# ArdinoCheaterBoardSche.net
KiCad netlist of a schematic drawn in EAGLE
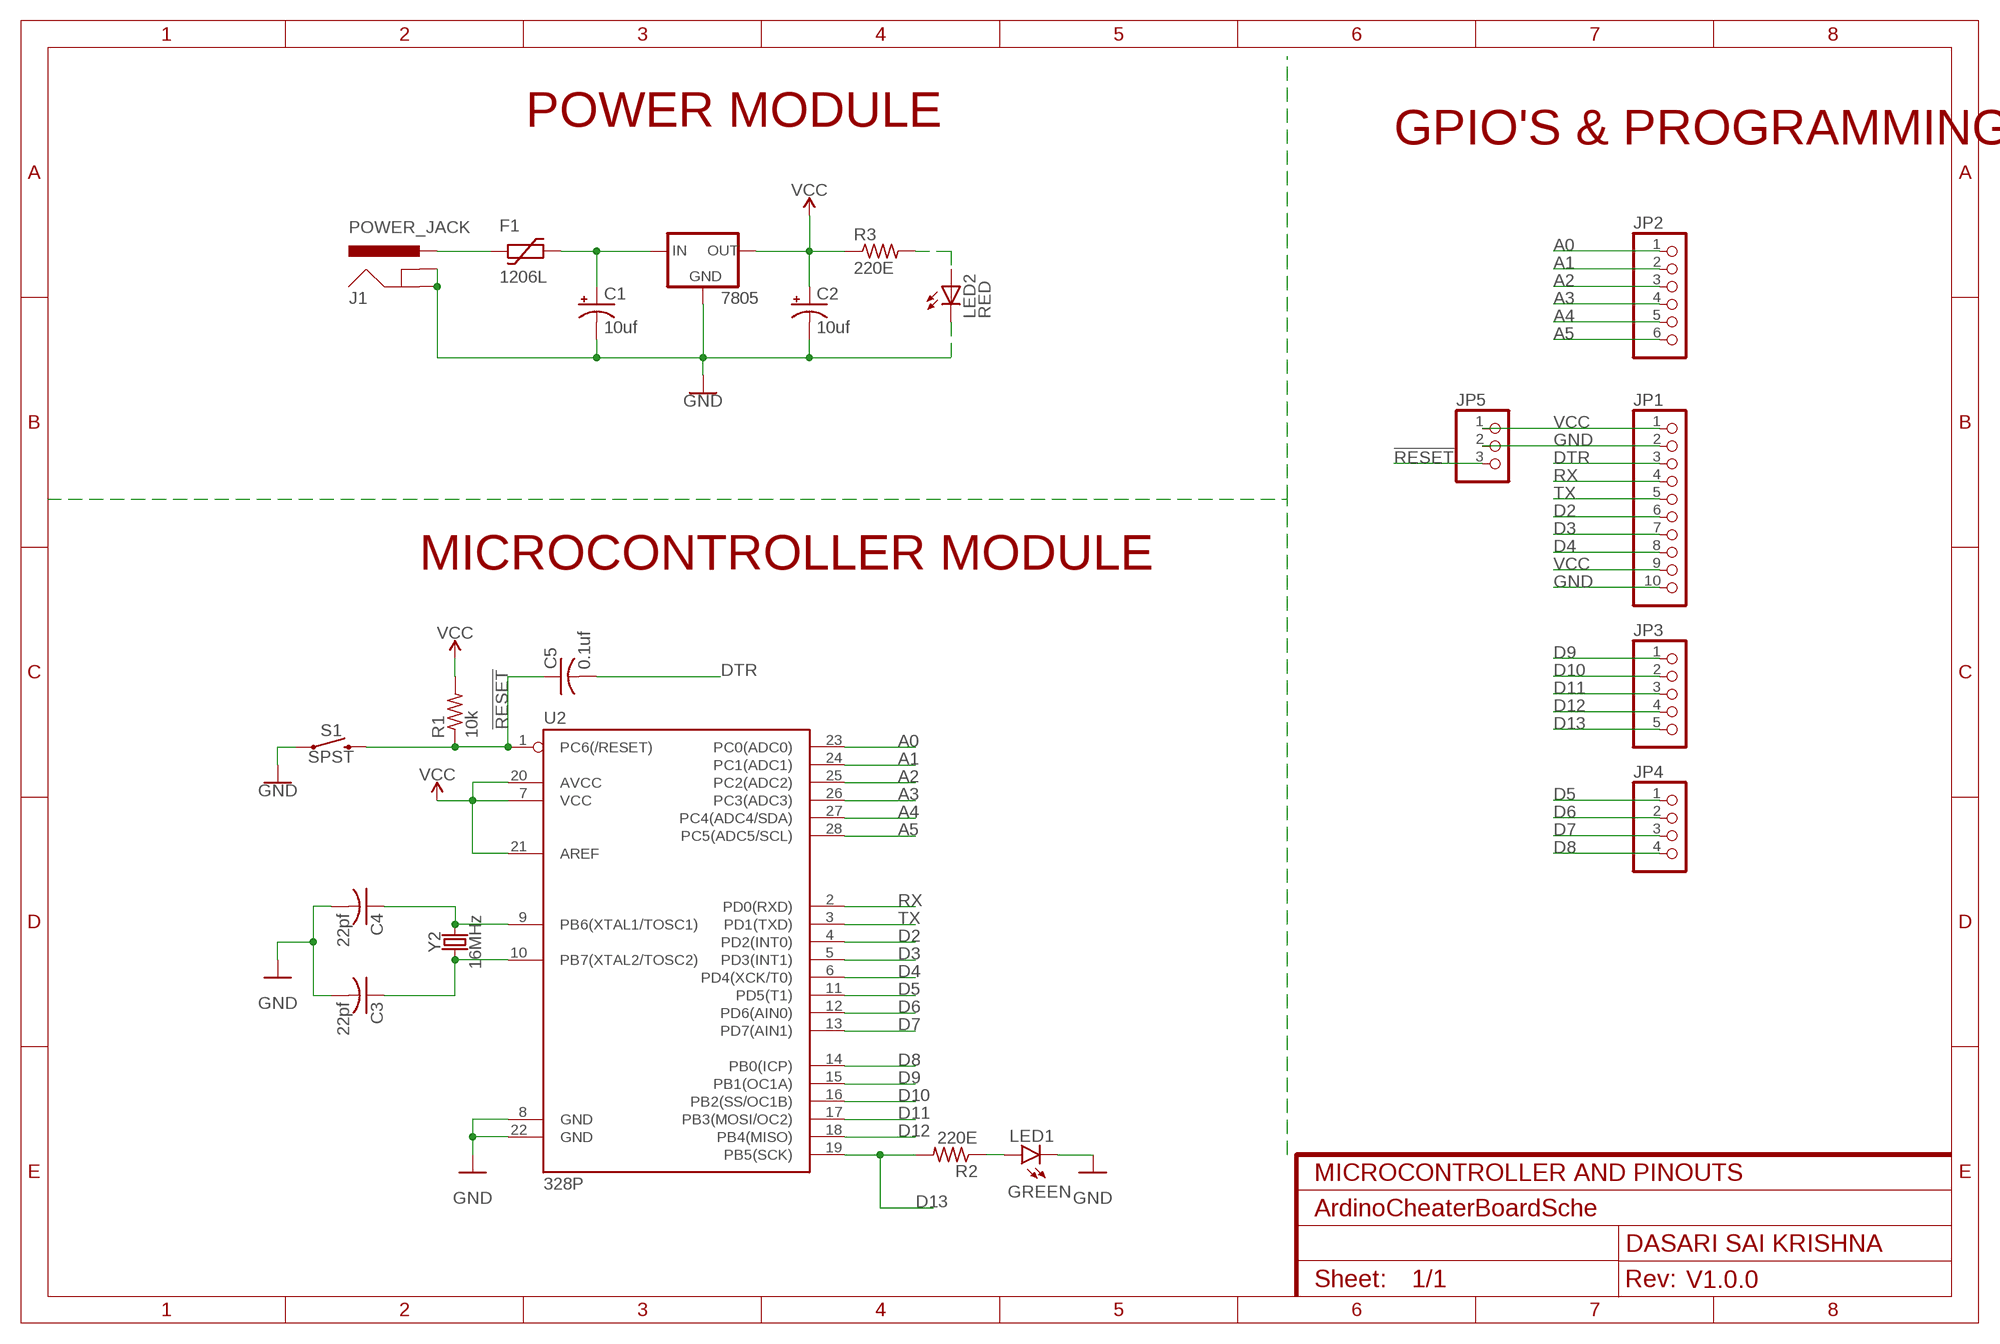
[diagram p0: schematic, sheet 1]

(export (version "E")
  (design (tool "Eeschema 10.0.6"))
  (components
    (comp (ref "C1")
      (value "10uf")
      (footprint "eagle-import:E2,5-6E")
      (libsource (lib "eagle-import") (part "CPOL-USE2,5-6E"))
    )
    (comp (ref "C2")
      (value "10uf")
      (footprint "eagle-import:E2,5-6E")
      (libsource (lib "eagle-import") (part "CPOL-USE2,5-6E"))
    )
    (comp (ref "C3")
      (value "22pf")
      (footprint "eagle-import:C025-024X044")
      (libsource (lib "eagle-import") (part "C-US025-024X044"))
    )
    (comp (ref "C4")
      (value "22pf")
      (footprint "eagle-import:C025-024X044")
      (libsource (lib "eagle-import") (part "C-US025-024X044"))
    )
    (comp (ref "C5")
      (value "0.1uf")
      (footprint "eagle-import:C025-024X044")
      (libsource (lib "eagle-import") (part "C-US025-024X044"))
    )
    (comp (ref "F1")
      (value "1206L")
      (footprint "eagle-import:1206L")
      (libsource (lib "eagle-import") (part "1206L"))
    )
    (comp (ref "IC1")
      (value "7805")
      (footprint "eagle-import:78XXS")
      (libsource (lib "eagle-import") (part "78XXS"))
    )
    (comp (ref "J1")
      (value "POWER_JACK")
      (footprint "eagle-import:POWER_JACK_PTH")
      (libsource (lib "eagle-import") (part "POWER_JACK"))
    )
    (comp (ref "JP1")
      (value "PINHD-1X10")
      (footprint "eagle-import:1X10")
      (libsource (lib "eagle-import") (part "PINHD-1X10"))
    )
    (comp (ref "JP2")
      (value "PINHD-1X6")
      (footprint "eagle-import:1X06")
      (libsource (lib "eagle-import") (part "PINHD-1X6"))
    )
    (comp (ref "JP3")
      (value "PINHD-1X5")
      (footprint "eagle-import:1X05")
      (libsource (lib "eagle-import") (part "PINHD-1X5"))
    )
    (comp (ref "JP4")
      (value "PINHD-1X4")
      (footprint "eagle-import:1X04")
      (libsource (lib "eagle-import") (part "PINHD-1X4"))
    )
    (comp (ref "JP5")
      (value "PINHD-1X3")
      (footprint "eagle-import:1X03")
      (libsource (lib "eagle-import") (part "PINHD-1X3"))
    )
    (comp (ref "LED1")
      (value "GREEN")
      (footprint "eagle-import:LED3MM")
      (libsource (lib "eagle-import") (part "led_259_LED3MM"))
    )
    (comp (ref "LED2")
      (value "RED")
      (footprint "eagle-import:LED3MM")
      (libsource (lib "eagle-import") (part "LED3MM"))
    )
    (comp (ref "R1")
      (value "10k")
      (footprint "eagle-import:0204_7")
      (libsource (lib "eagle-import") (part "R-US_0204/7"))
    )
    (comp (ref "R2")
      (value "220E")
      (footprint "eagle-import:0204_7")
      (libsource (lib "eagle-import") (part "R-US_0204/7"))
    )
    (comp (ref "R3")
      (value "220E")
      (footprint "eagle-import:0204_7")
      (libsource (lib "eagle-import") (part "R-US_0204/7"))
    )
    (comp (ref "S1")
      (value "SPST")
      (footprint "eagle-import:TACTILE_SWITCH_PTH_6.0MM")
      (libsource (lib "eagle-import") (part "MOMENTARY-SWITCH-SPST-PTH-6.0MM"))
    )
    (comp (ref "U2")
      (value "328P")
      (footprint "eagle-import:DIP28")
      (libsource (lib "eagle-import") (part "ATMEGA328P_PDIP"))
    )
    (comp (ref "Y2")
      (value "16MHz")
      (footprint "eagle-import:HC49US")
      (libsource (lib "eagle-import") (part "CRYSTAL-16MHZPTH-HC49US"))
    )
  )
  (nets
    (net (code "1") (name "/A0") (class "Default")
      (node (ref "JP2") (pin "1") (pinfunction "1_1") (pintype "passive"))
      (node (ref "U2") (pin "23") (pinfunction "PC0(ADC0)_23") (pintype "bidirectional"))
    )
    (net (code "2") (name "/A1") (class "Default")
      (node (ref "JP2") (pin "2") (pinfunction "2_2") (pintype "passive"))
      (node (ref "U2") (pin "24") (pinfunction "PC1(ADC1)_24") (pintype "bidirectional"))
    )
    (net (code "3") (name "/A2") (class "Default")
      (node (ref "JP2") (pin "3") (pinfunction "3_3") (pintype "passive"))
      (node (ref "U2") (pin "25") (pinfunction "PC2(ADC2)_25") (pintype "bidirectional"))
    )
    (net (code "4") (name "/A3") (class "Default")
      (node (ref "JP2") (pin "4") (pinfunction "4_4") (pintype "passive"))
      (node (ref "U2") (pin "26") (pinfunction "PC3(ADC3)_26") (pintype "bidirectional"))
    )
    (net (code "5") (name "/A4") (class "Default")
      (node (ref "JP2") (pin "5") (pinfunction "5_5") (pintype "passive"))
      (node (ref "U2") (pin "27") (pinfunction "PC4(ADC4/SDA)_27") (pintype "bidirectional"))
    )
    (net (code "6") (name "/A5") (class "Default")
      (node (ref "JP2") (pin "6") (pinfunction "6_6") (pintype "passive"))
      (node (ref "U2") (pin "28") (pinfunction "PC5(ADC5/SCL)_28") (pintype "bidirectional"))
    )
    (net (code "7") (name "/D2") (class "Default")
      (node (ref "JP1") (pin "6") (pinfunction "6_6") (pintype "passive"))
      (node (ref "U2") (pin "4") (pinfunction "PD2(INT0)_4") (pintype "bidirectional"))
    )
    (net (code "8") (name "/D3") (class "Default")
      (node (ref "JP1") (pin "7") (pinfunction "7_7") (pintype "passive"))
      (node (ref "U2") (pin "5") (pinfunction "PD3(INT1)_5") (pintype "bidirectional"))
    )
    (net (code "9") (name "/D4") (class "Default")
      (node (ref "JP1") (pin "8") (pinfunction "8_8") (pintype "passive"))
      (node (ref "U2") (pin "6") (pinfunction "PD4(XCK/T0)_6") (pintype "bidirectional"))
    )
    (net (code "10") (name "/D5") (class "Default")
      (node (ref "JP4") (pin "1") (pinfunction "1_1") (pintype "passive"))
      (node (ref "U2") (pin "11") (pinfunction "PD5(T1)_11") (pintype "bidirectional"))
    )
    (net (code "11") (name "/D6") (class "Default")
      (node (ref "JP4") (pin "2") (pinfunction "2_2") (pintype "passive"))
      (node (ref "U2") (pin "12") (pinfunction "PD6(AIN0)_12") (pintype "bidirectional"))
    )
    (net (code "12") (name "/D7") (class "Default")
      (node (ref "JP4") (pin "3") (pinfunction "3_3") (pintype "passive"))
      (node (ref "U2") (pin "13") (pinfunction "PD7(AIN1)_13") (pintype "bidirectional"))
    )
    (net (code "13") (name "/D8") (class "Default")
      (node (ref "JP4") (pin "4") (pinfunction "4_4") (pintype "passive"))
      (node (ref "U2") (pin "14") (pinfunction "PB0(ICP)_14") (pintype "bidirectional"))
    )
    (net (code "14") (name "/D9") (class "Default")
      (node (ref "JP3") (pin "1") (pinfunction "1_1") (pintype "passive"))
      (node (ref "U2") (pin "15") (pinfunction "PB1(OC1A)_15") (pintype "bidirectional"))
    )
    (net (code "15") (name "/D10") (class "Default")
      (node (ref "JP3") (pin "2") (pinfunction "2_2") (pintype "passive"))
      (node (ref "U2") (pin "16") (pinfunction "PB2(SS/OC1B)_16") (pintype "bidirectional"))
    )
    (net (code "16") (name "/D11") (class "Default")
      (node (ref "JP3") (pin "3") (pinfunction "3_3") (pintype "passive"))
      (node (ref "U2") (pin "17") (pinfunction "PB3(MOSI/OC2)_17") (pintype "bidirectional"))
    )
    (net (code "17") (name "/D12") (class "Default")
      (node (ref "JP3") (pin "4") (pinfunction "4_4") (pintype "passive"))
      (node (ref "U2") (pin "18") (pinfunction "PB4(MISO)_18") (pintype "bidirectional"))
    )
    (net (code "18") (name "/D13") (class "Default")
      (node (ref "JP3") (pin "5") (pinfunction "5_5") (pintype "passive"))
      (node (ref "R2") (pin "2") (pinfunction "2_2") (pintype "passive"))
      (node (ref "U2") (pin "19") (pinfunction "PB5(SCK)_19") (pintype "bidirectional"))
    )
    (net (code "19") (name "/DTR") (class "Default")
      (node (ref "C5") (pin "2") (pinfunction "2_2") (pintype "passive"))
      (node (ref "JP1") (pin "3") (pinfunction "3_3") (pintype "passive"))
    )
    (net (code "20") (name "/RX") (class "Default")
      (node (ref "JP1") (pin "4") (pinfunction "4_4") (pintype "passive"))
      (node (ref "U2") (pin "2") (pinfunction "PD0(RXD)_2") (pintype "bidirectional"))
    )
    (net (code "21") (name "/TX") (class "Default")
      (node (ref "JP1") (pin "5") (pinfunction "5_5") (pintype "passive"))
      (node (ref "U2") (pin "3") (pinfunction "PD1(TXD)_3") (pintype "bidirectional"))
    )
    (net (code "22") (name "/~{RESET}") (class "Default")
      (node (ref "C5") (pin "1") (pinfunction "1_1") (pintype "passive"))
      (node (ref "JP5") (pin "3") (pinfunction "3_3") (pintype "passive"))
      (node (ref "R1") (pin "1") (pinfunction "1_1") (pintype "passive"))
      (node (ref "S1") (pin "3") (pinfunction "2_3") (pintype "passive"))
      (node (ref "U2") (pin "1") (pinfunction "PC6(/RESET)_1") (pintype "bidirectional"))
    )
    (net (code "23") (name "GND") (class "Default")
      (node (ref "C1") (pin "-") (pinfunction "-_-") (pintype "passive"))
      (node (ref "C2") (pin "-") (pinfunction "-_-") (pintype "passive"))
      (node (ref "C3") (pin "2") (pinfunction "2_2") (pintype "passive"))
      (node (ref "C4") (pin "2") (pinfunction "2_2") (pintype "passive"))
      (node (ref "IC1") (pin "GND") (pinfunction "GND_GND") (pintype "input"))
      (node (ref "J1") (pin "GND") (pinfunction "GND_GND") (pintype "bidirectional"))
      (node (ref "J1") (pin "GNDBREAK") (pinfunction "GNDBREAK_GNDBREAK") (pintype "bidirectional"))
      (node (ref "JP1") (pin "10") (pinfunction "10_10") (pintype "passive"))
      (node (ref "JP1") (pin "2") (pinfunction "2_2") (pintype "passive"))
      (node (ref "JP5") (pin "2") (pinfunction "2_2") (pintype "passive"))
      (node (ref "LED1") (pin "K") (pinfunction "C_K") (pintype "passive"))
      (node (ref "LED2") (pin "K") (pinfunction "C_K") (pintype "passive"))
      (node (ref "S1") (pin "1") (pinfunction "1_1") (pintype "passive"))
      (node (ref "U2") (pin "22") (pinfunction "GND_22") (pintype "bidirectional"))
      (node (ref "U2") (pin "8") (pinfunction "GND_8") (pintype "bidirectional"))
    )
    (net (code "24") (name "Net-(F1-1)") (class "Default")
      (node (ref "F1") (pin "P$1") (pinfunction "1_P$1") (pintype "passive"))
      (node (ref "J1") (pin "PWR") (pinfunction "PWR_PWR") (pintype "bidirectional"))
    )
    (net (code "25") (name "Net-(F1-2)") (class "Default")
      (node (ref "C1") (pin "+") (pinfunction "+_+") (pintype "passive"))
      (node (ref "F1") (pin "P$2") (pinfunction "2_P$2") (pintype "passive"))
      (node (ref "IC1") (pin "IN") (pinfunction "IN_IN") (pintype "input"))
    )
    (net (code "26") (name "Net-(LED1-PadA)") (class "Default")
      (node (ref "LED1") (pin "A") (pinfunction "A_A") (pintype "passive"))
      (node (ref "R2") (pin "1") (pinfunction "1_1") (pintype "passive"))
    )
    (net (code "27") (name "Net-(LED2-PadA)") (class "Default")
      (node (ref "LED2") (pin "A") (pinfunction "A_A") (pintype "passive"))
      (node (ref "R3") (pin "2") (pinfunction "2_2") (pintype "passive"))
    )
    (net (code "28") (name "Net-(U2-PB6(XTAL1{slash}TOSC1))") (class "Default")
      (node (ref "C4") (pin "1") (pinfunction "1_1") (pintype "passive"))
      (node (ref "U2") (pin "9") (pinfunction "PB6(XTAL1/TOSC1)_9") (pintype "bidirectional"))
      (node (ref "Y2") (pin "2") (pinfunction "2_2") (pintype "passive"))
    )
    (net (code "29") (name "Net-(U2-PB7(XTAL2{slash}TOSC2))") (class "Default")
      (node (ref "C3") (pin "1") (pinfunction "1_1") (pintype "passive"))
      (node (ref "U2") (pin "10") (pinfunction "PB7(XTAL2/TOSC2)_10") (pintype "bidirectional"))
      (node (ref "Y2") (pin "1") (pinfunction "1_1") (pintype "passive"))
    )
    (net (code "30") (name "VCC") (class "Default")
      (node (ref "C2") (pin "+") (pinfunction "+_+") (pintype "passive"))
      (node (ref "IC1") (pin "OUT") (pinfunction "OUT_OUT") (pintype "passive"))
      (node (ref "JP1") (pin "1") (pinfunction "1_1") (pintype "passive"))
      (node (ref "JP1") (pin "9") (pinfunction "9_9") (pintype "passive"))
      (node (ref "JP5") (pin "1") (pinfunction "1_1") (pintype "passive"))
      (node (ref "R1") (pin "2") (pinfunction "2_2") (pintype "passive"))
      (node (ref "R3") (pin "1") (pinfunction "1_1") (pintype "passive"))
      (node (ref "U2") (pin "20") (pinfunction "AVCC_20") (pintype "bidirectional"))
      (node (ref "U2") (pin "21") (pinfunction "AREF_21") (pintype "bidirectional"))
      (node (ref "U2") (pin "7") (pinfunction "VCC_7") (pintype "bidirectional"))
    )
  )
)
